# RC-7606M-LED.net
KiCad netlist of a schematic drawn in EasyEDA
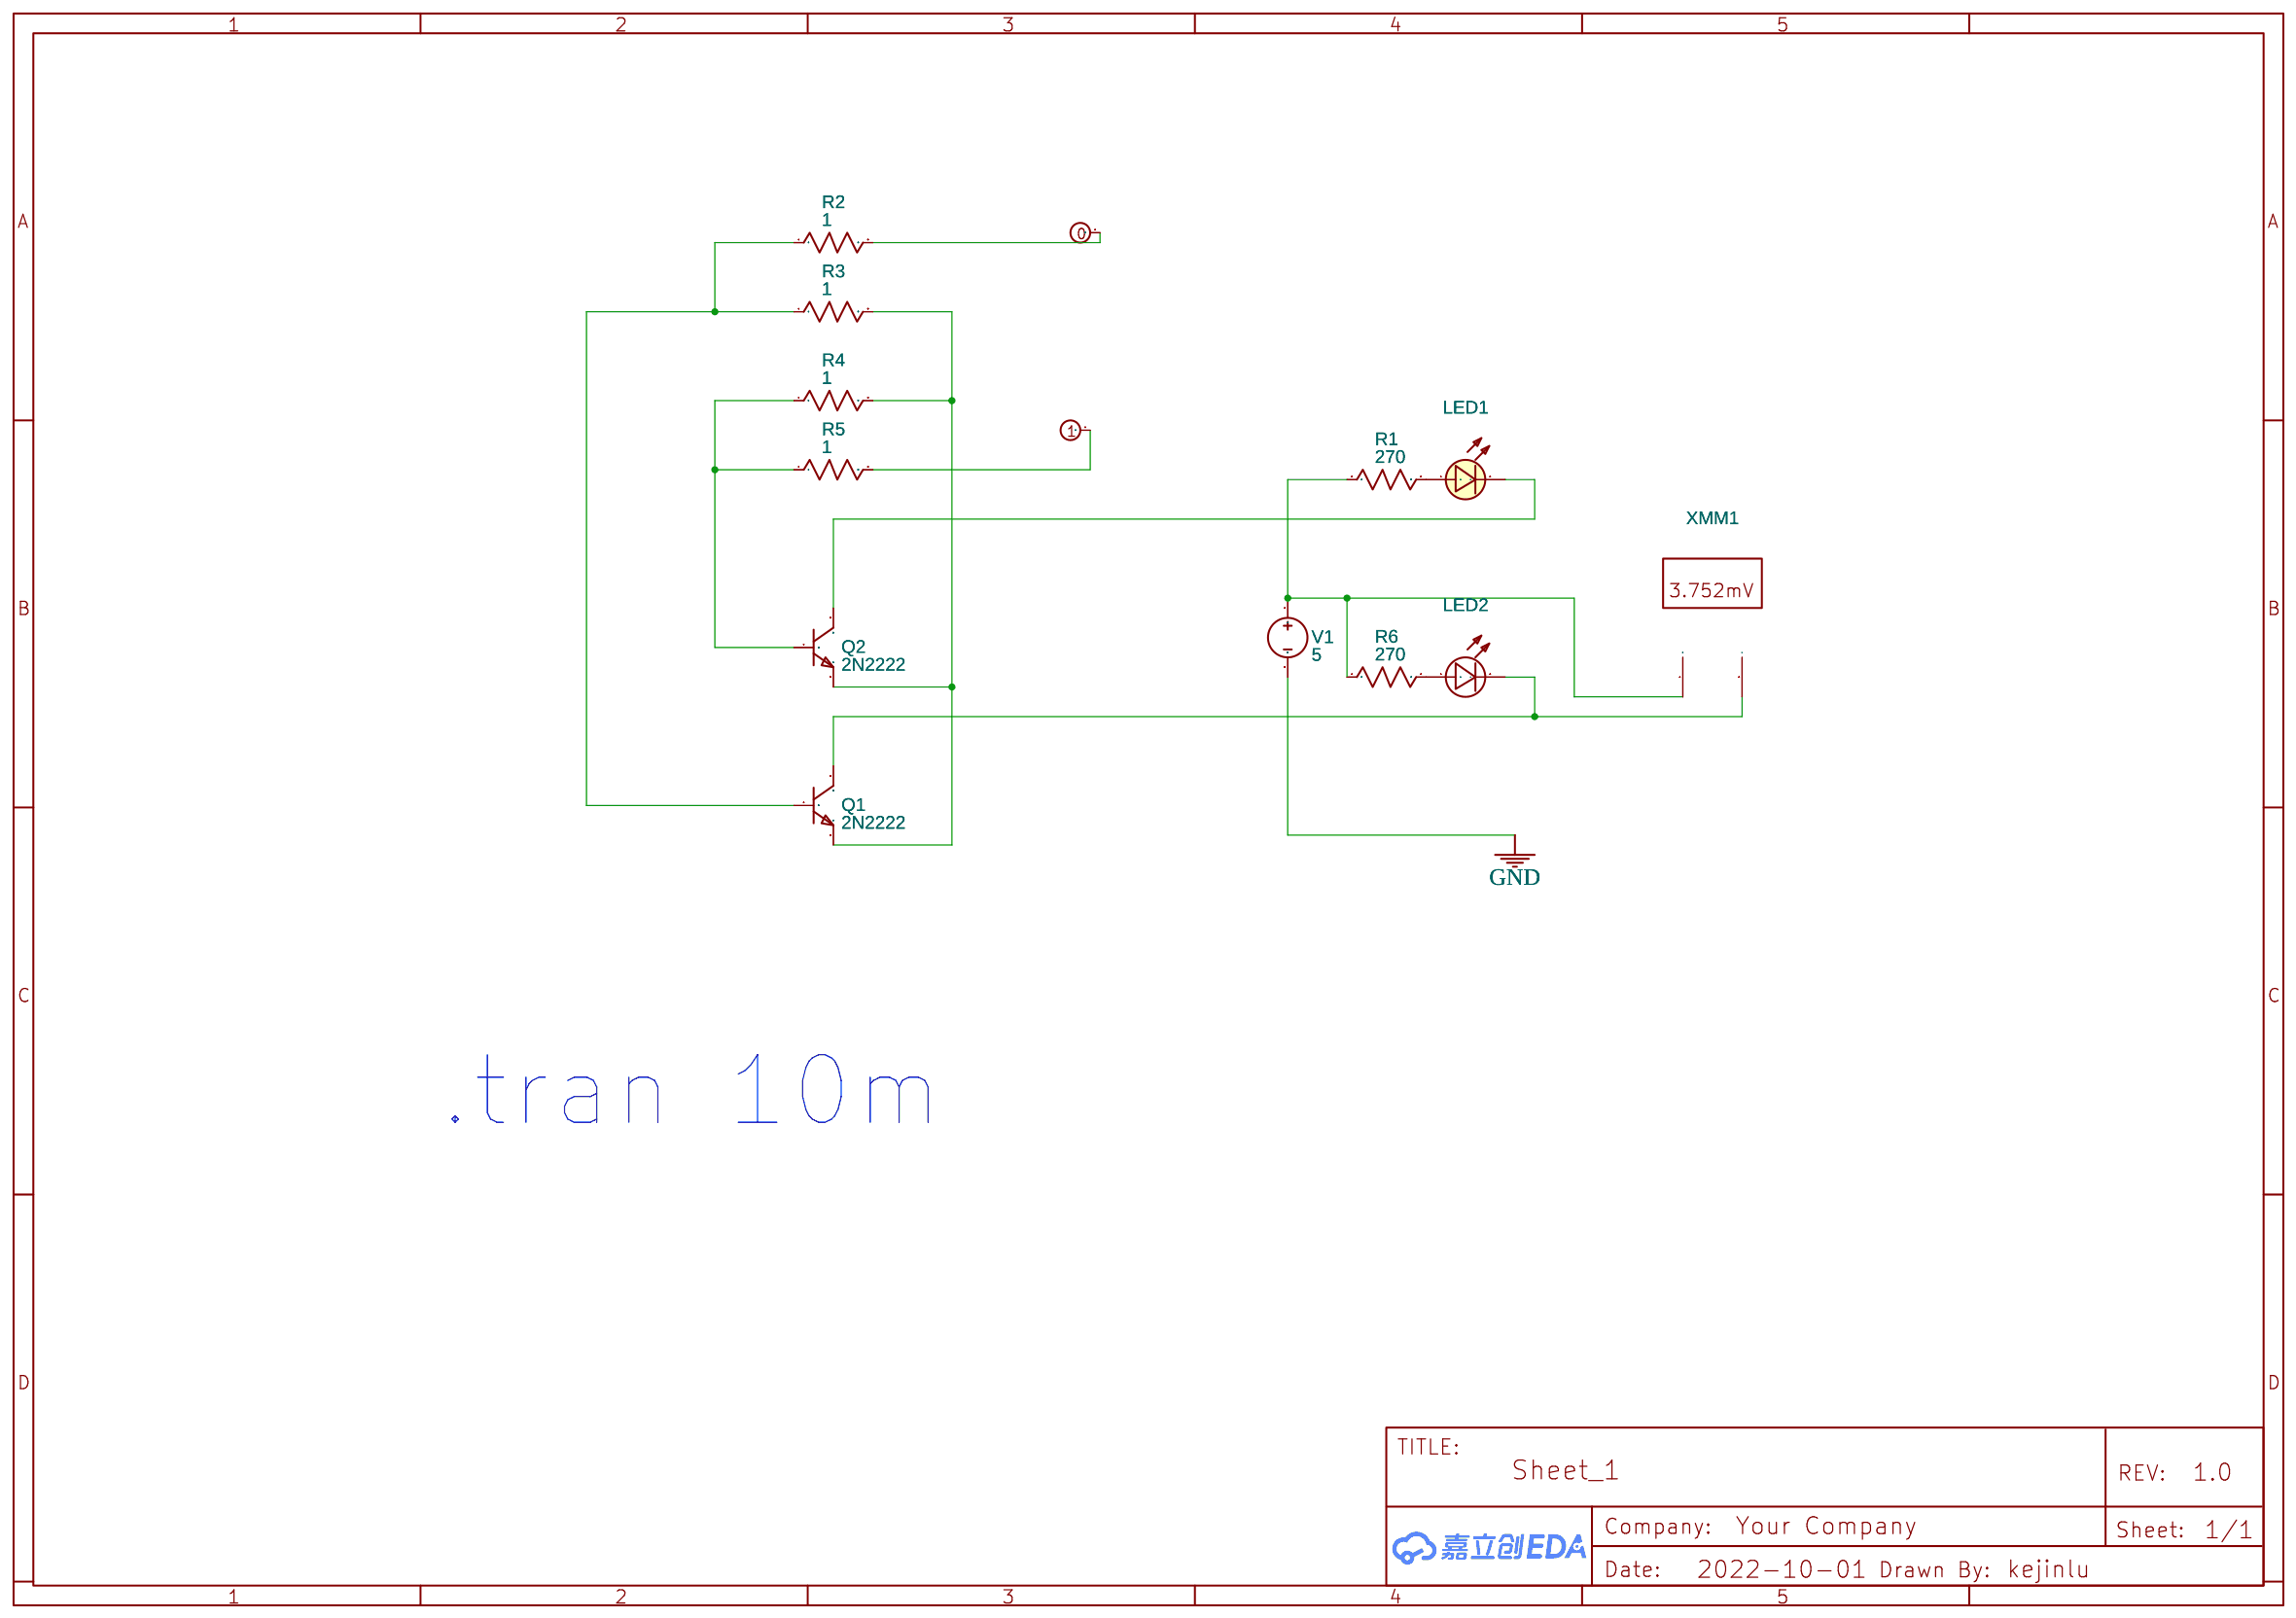
[diagram p0: Sheet_2]
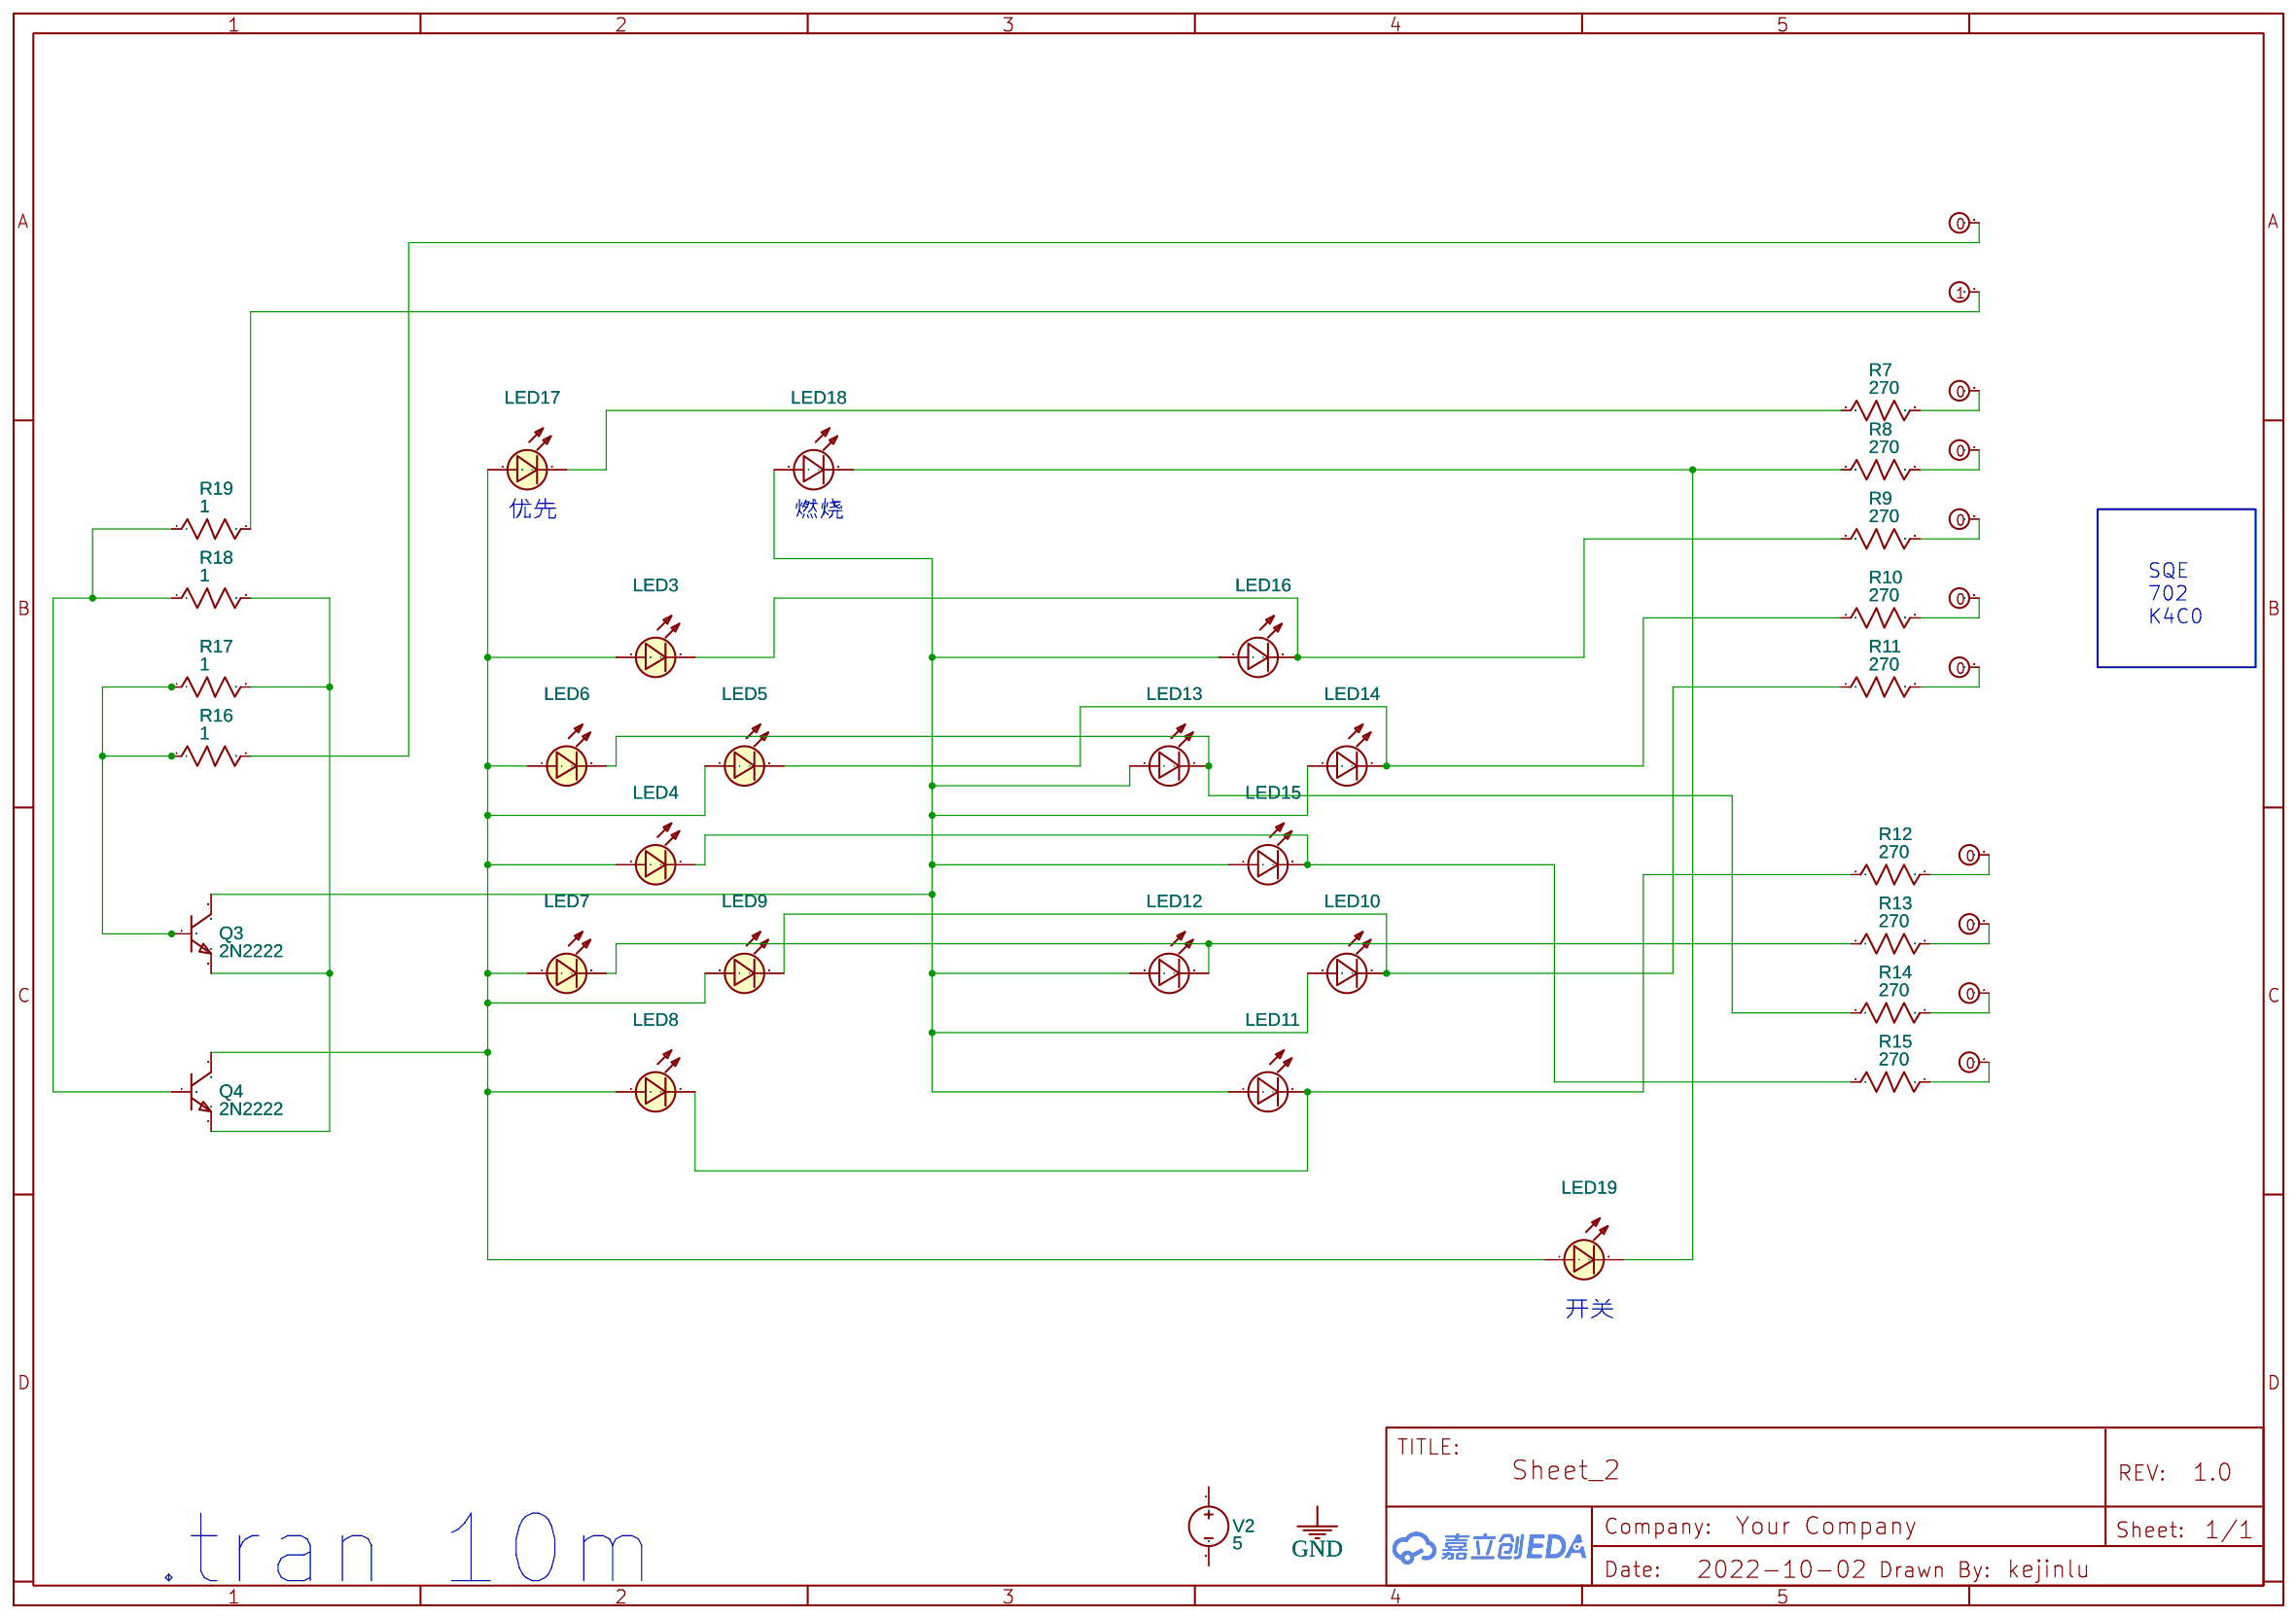
[diagram p1: Sheet_1]

(export (version "E")
  (design (tool "Eeschema 10.0.6"))
  (components
    (comp (ref "LED1") (value "LED") (libsource (lib "") (part "LED")))
    (comp (ref "LED2") (value "LED") (libsource (lib "") (part "LED_1")))
    (comp (ref "Q1") (value "2N2222") (libsource (lib "") (part "2N2222")))
    (comp (ref "Q2") (value "2N2222") (libsource (lib "") (part "2N2222")))
    (comp (ref "R1") (value "270") (libsource (lib "") (part "Resistor_US")))
    (comp (ref "R2") (value "1") (libsource (lib "") (part "Resistor_US")))
    (comp (ref "R3") (value "1") (libsource (lib "") (part "Resistor_US")))
    (comp (ref "R4") (value "1") (libsource (lib "") (part "Resistor_US")))
    (comp (ref "R5") (value "1") (libsource (lib "") (part "Resistor_US")))
    (comp (ref "R6") (value "270") (libsource (lib "") (part "Resistor_US")))
    (comp (ref "U1") (value "Logicstate1") (libsource (lib "") (part "LOGICSTATE_1")))
    (comp (ref "U2") (value "Logicstate1") (libsource (lib "") (part "LOGICSTATE")))
    (comp (ref "V1") (value "5") (libsource (lib "") (part "VDC")))
    (comp (ref "XMM1") (value "Multimeter") (libsource (lib "") (part "MULTIMETER")))
    (comp (ref "LED3") (value "LED") (libsource (lib "") (part "LED")))
    (comp (ref "LED4") (value "LED") (libsource (lib "") (part "LED")))
    (comp (ref "LED5") (value "LED") (libsource (lib "") (part "LED")))
    (comp (ref "LED6") (value "LED") (libsource (lib "") (part "LED")))
    (comp (ref "LED7") (value "LED") (libsource (lib "") (part "LED")))
    (comp (ref "LED8") (value "LED") (libsource (lib "") (part "LED")))
    (comp (ref "LED9") (value "LED") (libsource (lib "") (part "LED")))
    (comp (ref "LED10") (value "LED") (libsource (lib "") (part "LED_1")))
    (comp (ref "LED11") (value "LED") (libsource (lib "") (part "LED_1")))
    (comp (ref "LED12") (value "LED") (libsource (lib "") (part "LED_1")))
    (comp (ref "LED13") (value "LED") (libsource (lib "") (part "LED_1")))
    (comp (ref "LED14") (value "LED") (libsource (lib "") (part "LED_1")))
    (comp (ref "LED15") (value "LED") (libsource (lib "") (part "LED_1")))
    (comp (ref "LED16") (value "LED") (libsource (lib "") (part "LED_1")))
    (comp (ref "LED17") (value "LED") (libsource (lib "") (part "LED")))
    (comp (ref "LED18") (value "LED") (libsource (lib "") (part "LED_1")))
    (comp (ref "LED19") (value "LED") (libsource (lib "") (part "LED")))
    (comp (ref "Q3") (value "2N2222") (libsource (lib "") (part "2N2222")))
    (comp (ref "Q4") (value "2N2222") (libsource (lib "") (part "2N2222")))
    (comp (ref "R7") (value "270") (libsource (lib "") (part "Resistor_US")))
    (comp (ref "R8") (value "270") (libsource (lib "") (part "Resistor_US")))
    (comp (ref "R9") (value "270") (libsource (lib "") (part "Resistor_US")))
    (comp (ref "R10") (value "270") (libsource (lib "") (part "Resistor_US")))
    (comp (ref "R11") (value "270") (libsource (lib "") (part "Resistor_US")))
    (comp (ref "R12") (value "270") (libsource (lib "") (part "Resistor_US")))
    (comp (ref "R13") (value "270") (libsource (lib "") (part "Resistor_US")))
    (comp (ref "R14") (value "270") (libsource (lib "") (part "Resistor_US")))
    (comp (ref "R15") (value "270") (libsource (lib "") (part "Resistor_US")))
    (comp (ref "R16") (value "1") (libsource (lib "") (part "Resistor_US")))
    (comp (ref "R17") (value "1") (libsource (lib "") (part "Resistor_US")))
    (comp (ref "R18") (value "1") (libsource (lib "") (part "Resistor_US")))
    (comp (ref "R19") (value "1") (libsource (lib "") (part "Resistor_US")))
    (comp (ref "U3") (value "Logicstate1") (libsource (lib "") (part "LOGICSTATE")))
    (comp (ref "U4") (value "Logicstate1") (libsource (lib "") (part "LOGICSTATE_1")))
    (comp (ref "U5") (value "Logicstate1") (libsource (lib "") (part "LOGICSTATE")))
    (comp (ref "U6") (value "Logicstate1") (libsource (lib "") (part "LOGICSTATE")))
    (comp (ref "U7") (value "Logicstate1") (libsource (lib "") (part "LOGICSTATE")))
    (comp (ref "U8") (value "Logicstate1") (libsource (lib "") (part "LOGICSTATE")))
    (comp (ref "U9") (value "Logicstate1") (libsource (lib "") (part "LOGICSTATE")))
    (comp (ref "U10") (value "Logicstate1") (libsource (lib "") (part "LOGICSTATE")))
    (comp (ref "U11") (value "Logicstate1") (libsource (lib "") (part "LOGICSTATE")))
    (comp (ref "U12") (value "Logicstate1") (libsource (lib "") (part "LOGICSTATE")))
    (comp (ref "U13") (value "Logicstate1") (libsource (lib "") (part "LOGICSTATE")))
    (comp (ref "V2") (value "5") (libsource (lib "") (part "VDC")))
  )
  (nets
    (net (code "1") (name "GND") (class "Default")
      (node (ref "V1") (pin "2") (pinfunction "2_2") (pintype "unspecified"))
    )
    (net (code "2") (name "Net-(LED1-+)") (class "Default")
      (node (ref "LED1") (pin "1") (pinfunction "+_1") (pintype "unspecified"))
      (node (ref "R1") (pin "2") (pinfunction "2_2") (pintype "unspecified"))
    )
    (net (code "3") (name "Net-(LED1--)") (class "Default")
      (node (ref "LED1") (pin "2") (pinfunction "-_2") (pintype "unspecified"))
      (node (ref "Q2") (pin "3") (pinfunction "C_3") (pintype "unspecified"))
    )
    (net (code "4") (name "Net-(LED2-+)") (class "Default")
      (node (ref "LED2") (pin "1") (pinfunction "+_1") (pintype "unspecified"))
      (node (ref "R6") (pin "2") (pinfunction "2_2") (pintype "unspecified"))
    )
    (net (code "5") (name "Net-(LED2--)") (class "Default")
      (node (ref "LED2") (pin "2") (pinfunction "-_2") (pintype "unspecified"))
      (node (ref "Q1") (pin "3") (pinfunction "C_3") (pintype "unspecified"))
      (node (ref "XMM1") (pin "2") (pinfunction "I_2") (pintype "unspecified"))
    )
    (net (code "6") (name "Net-(LED10-+)") (class "Default")
      (node (ref "LED10") (pin "1") (pinfunction "+_1") (pintype "unspecified"))
      (node (ref "LED11") (pin "1") (pinfunction "+_1") (pintype "unspecified"))
      (node (ref "LED12") (pin "1") (pinfunction "+_1") (pintype "unspecified"))
      (node (ref "LED13") (pin "1") (pinfunction "+_1") (pintype "unspecified"))
      (node (ref "LED14") (pin "1") (pinfunction "+_1") (pintype "unspecified"))
      (node (ref "LED15") (pin "1") (pinfunction "+_1") (pintype "unspecified"))
      (node (ref "LED16") (pin "1") (pinfunction "+_1") (pintype "unspecified"))
      (node (ref "LED18") (pin "1") (pinfunction "+_1") (pintype "unspecified"))
      (node (ref "Q3") (pin "3") (pinfunction "C_3") (pintype "unspecified"))
    )
    (net (code "7") (name "Net-(LED10--)") (class "Default")
      (node (ref "LED10") (pin "2") (pinfunction "-_2") (pintype "unspecified"))
      (node (ref "LED9") (pin "2") (pinfunction "-_2") (pintype "unspecified"))
      (node (ref "R11") (pin "1") (pinfunction "1_1") (pintype "unspecified"))
    )
    (net (code "8") (name "Net-(LED11--)") (class "Default")
      (node (ref "LED11") (pin "2") (pinfunction "-_2") (pintype "unspecified"))
      (node (ref "LED8") (pin "2") (pinfunction "-_2") (pintype "unspecified"))
      (node (ref "R12") (pin "1") (pinfunction "1_1") (pintype "unspecified"))
    )
    (net (code "9") (name "Net-(LED12--)") (class "Default")
      (node (ref "LED12") (pin "2") (pinfunction "-_2") (pintype "unspecified"))
      (node (ref "LED7") (pin "2") (pinfunction "-_2") (pintype "unspecified"))
      (node (ref "R13") (pin "1") (pinfunction "1_1") (pintype "unspecified"))
    )
    (net (code "10") (name "Net-(LED13--)") (class "Default")
      (node (ref "LED13") (pin "2") (pinfunction "-_2") (pintype "unspecified"))
      (node (ref "LED6") (pin "2") (pinfunction "-_2") (pintype "unspecified"))
      (node (ref "R14") (pin "1") (pinfunction "1_1") (pintype "unspecified"))
    )
    (net (code "11") (name "Net-(LED14--)") (class "Default")
      (node (ref "LED14") (pin "2") (pinfunction "-_2") (pintype "unspecified"))
      (node (ref "LED5") (pin "2") (pinfunction "-_2") (pintype "unspecified"))
      (node (ref "R10") (pin "1") (pinfunction "1_1") (pintype "unspecified"))
    )
    (net (code "12") (name "Net-(LED15--)") (class "Default")
      (node (ref "LED15") (pin "2") (pinfunction "-_2") (pintype "unspecified"))
      (node (ref "LED4") (pin "2") (pinfunction "-_2") (pintype "unspecified"))
      (node (ref "R15") (pin "1") (pinfunction "1_1") (pintype "unspecified"))
    )
    (net (code "13") (name "Net-(LED16--)") (class "Default")
      (node (ref "LED16") (pin "2") (pinfunction "-_2") (pintype "unspecified"))
      (node (ref "LED3") (pin "2") (pinfunction "-_2") (pintype "unspecified"))
      (node (ref "R9") (pin "1") (pinfunction "1_1") (pintype "unspecified"))
    )
    (net (code "14") (name "Net-(LED17-+)") (class "Default")
      (node (ref "LED17") (pin "1") (pinfunction "+_1") (pintype "unspecified"))
      (node (ref "LED19") (pin "1") (pinfunction "+_1") (pintype "unspecified"))
      (node (ref "LED3") (pin "1") (pinfunction "+_1") (pintype "unspecified"))
      (node (ref "LED4") (pin "1") (pinfunction "+_1") (pintype "unspecified"))
      (node (ref "LED5") (pin "1") (pinfunction "+_1") (pintype "unspecified"))
      (node (ref "LED6") (pin "1") (pinfunction "+_1") (pintype "unspecified"))
      (node (ref "LED7") (pin "1") (pinfunction "+_1") (pintype "unspecified"))
      (node (ref "LED8") (pin "1") (pinfunction "+_1") (pintype "unspecified"))
      (node (ref "LED9") (pin "1") (pinfunction "+_1") (pintype "unspecified"))
      (node (ref "Q4") (pin "3") (pinfunction "C_3") (pintype "unspecified"))
    )
    (net (code "15") (name "Net-(LED17--)") (class "Default")
      (node (ref "LED17") (pin "2") (pinfunction "-_2") (pintype "unspecified"))
      (node (ref "R7") (pin "1") (pinfunction "1_1") (pintype "unspecified"))
    )
    (net (code "16") (name "Net-(LED18--)") (class "Default")
      (node (ref "LED18") (pin "2") (pinfunction "-_2") (pintype "unspecified"))
      (node (ref "LED19") (pin "2") (pinfunction "-_2") (pintype "unspecified"))
      (node (ref "R8") (pin "1") (pinfunction "1_1") (pintype "unspecified"))
    )
    (net (code "17") (name "Net-(Q1-B)") (class "Default")
      (node (ref "Q1") (pin "1") (pinfunction "B_1") (pintype "unspecified"))
      (node (ref "R2") (pin "1") (pinfunction "1_1") (pintype "unspecified"))
      (node (ref "R3") (pin "1") (pinfunction "1_1") (pintype "unspecified"))
    )
    (net (code "18") (name "Net-(Q1-E)") (class "Default")
      (node (ref "Q1") (pin "2") (pinfunction "E_2") (pintype "unspecified"))
      (node (ref "Q2") (pin "2") (pinfunction "E_2") (pintype "unspecified"))
      (node (ref "R3") (pin "2") (pinfunction "2_2") (pintype "unspecified"))
      (node (ref "R4") (pin "2") (pinfunction "2_2") (pintype "unspecified"))
    )
    (net (code "19") (name "Net-(Q2-B)") (class "Default")
      (node (ref "Q2") (pin "1") (pinfunction "B_1") (pintype "unspecified"))
      (node (ref "R4") (pin "1") (pinfunction "1_1") (pintype "unspecified"))
      (node (ref "R5") (pin "1") (pinfunction "1_1") (pintype "unspecified"))
    )
    (net (code "20") (name "Net-(Q3-B)") (class "Default")
      (node (ref "Q3") (pin "1") (pinfunction "B_1") (pintype "unspecified"))
      (node (ref "R16") (pin "1") (pinfunction "1_1") (pintype "unspecified"))
      (node (ref "R17") (pin "1") (pinfunction "1_1") (pintype "unspecified"))
    )
    (net (code "21") (name "Net-(Q3-E)") (class "Default")
      (node (ref "Q3") (pin "2") (pinfunction "E_2") (pintype "unspecified"))
      (node (ref "Q4") (pin "2") (pinfunction "E_2") (pintype "unspecified"))
      (node (ref "R17") (pin "2") (pinfunction "2_2") (pintype "unspecified"))
      (node (ref "R18") (pin "2") (pinfunction "2_2") (pintype "unspecified"))
    )
    (net (code "22") (name "Net-(Q4-B)") (class "Default")
      (node (ref "Q4") (pin "1") (pinfunction "B_1") (pintype "unspecified"))
      (node (ref "R18") (pin "1") (pinfunction "1_1") (pintype "unspecified"))
      (node (ref "R19") (pin "1") (pinfunction "1_1") (pintype "unspecified"))
    )
    (net (code "23") (name "Net-(R2-Pad2)") (class "Default")
      (node (ref "R2") (pin "2") (pinfunction "2_2") (pintype "unspecified"))
      (node (ref "U1") (pin "1") (pinfunction "1_1") (pintype "unspecified"))
    )
    (net (code "24") (name "Net-(R5-Pad2)") (class "Default")
      (node (ref "R5") (pin "2") (pinfunction "2_2") (pintype "unspecified"))
      (node (ref "U2") (pin "1") (pinfunction "1_1") (pintype "unspecified"))
    )
    (net (code "25") (name "Net-(R7-Pad2)") (class "Default")
      (node (ref "R7") (pin "2") (pinfunction "2_2") (pintype "unspecified"))
      (node (ref "U5") (pin "1") (pinfunction "1_1") (pintype "unspecified"))
    )
    (net (code "26") (name "Net-(R8-Pad2)") (class "Default")
      (node (ref "R8") (pin "2") (pinfunction "2_2") (pintype "unspecified"))
      (node (ref "U6") (pin "1") (pinfunction "1_1") (pintype "unspecified"))
    )
    (net (code "27") (name "Net-(R9-Pad2)") (class "Default")
      (node (ref "R9") (pin "2") (pinfunction "2_2") (pintype "unspecified"))
      (node (ref "U7") (pin "1") (pinfunction "1_1") (pintype "unspecified"))
    )
    (net (code "28") (name "Net-(R10-Pad2)") (class "Default")
      (node (ref "R10") (pin "2") (pinfunction "2_2") (pintype "unspecified"))
      (node (ref "U8") (pin "1") (pinfunction "1_1") (pintype "unspecified"))
    )
    (net (code "29") (name "Net-(R11-Pad2)") (class "Default")
      (node (ref "R11") (pin "2") (pinfunction "2_2") (pintype "unspecified"))
      (node (ref "U9") (pin "1") (pinfunction "1_1") (pintype "unspecified"))
    )
    (net (code "30") (name "Net-(R12-Pad2)") (class "Default")
      (node (ref "R12") (pin "2") (pinfunction "2_2") (pintype "unspecified"))
      (node (ref "U10") (pin "1") (pinfunction "1_1") (pintype "unspecified"))
    )
    (net (code "31") (name "Net-(R13-Pad2)") (class "Default")
      (node (ref "R13") (pin "2") (pinfunction "2_2") (pintype "unspecified"))
      (node (ref "U11") (pin "1") (pinfunction "1_1") (pintype "unspecified"))
    )
    (net (code "32") (name "Net-(R14-Pad2)") (class "Default")
      (node (ref "R14") (pin "2") (pinfunction "2_2") (pintype "unspecified"))
      (node (ref "U12") (pin "1") (pinfunction "1_1") (pintype "unspecified"))
    )
    (net (code "33") (name "Net-(R15-Pad2)") (class "Default")
      (node (ref "R15") (pin "2") (pinfunction "2_2") (pintype "unspecified"))
      (node (ref "U13") (pin "1") (pinfunction "1_1") (pintype "unspecified"))
    )
    (net (code "34") (name "Net-(R16-Pad2)") (class "Default")
      (node (ref "R16") (pin "2") (pinfunction "2_2") (pintype "unspecified"))
      (node (ref "U3") (pin "1") (pinfunction "1_1") (pintype "unspecified"))
    )
    (net (code "35") (name "Net-(R19-Pad2)") (class "Default")
      (node (ref "R19") (pin "2") (pinfunction "2_2") (pintype "unspecified"))
      (node (ref "U4") (pin "1") (pinfunction "1_1") (pintype "unspecified"))
    )
    (net (code "36") (name "Net-(XMM1-+)") (class "Default")
      (node (ref "R1") (pin "1") (pinfunction "1_1") (pintype "unspecified"))
      (node (ref "R6") (pin "1") (pinfunction "1_1") (pintype "unspecified"))
      (node (ref "V1") (pin "1") (pinfunction "1_1") (pintype "unspecified"))
      (node (ref "XMM1") (pin "1") (pinfunction "+_1") (pintype "unspecified"))
    )
    (net (code "37") (name "unconnected-(V2-Pad1)") (class "Default")
      (node (ref "V2") (pin "1") (pinfunction "1_1") (pintype "unspecified"))
    )
    (net (code "38") (name "unconnected-(V2-Pad2)") (class "Default")
      (node (ref "V2") (pin "2") (pinfunction "2_2") (pintype "unspecified"))
    )
  )
)
